# alarm1.net
KiCad netlist of a schematic drawn in EAGLE
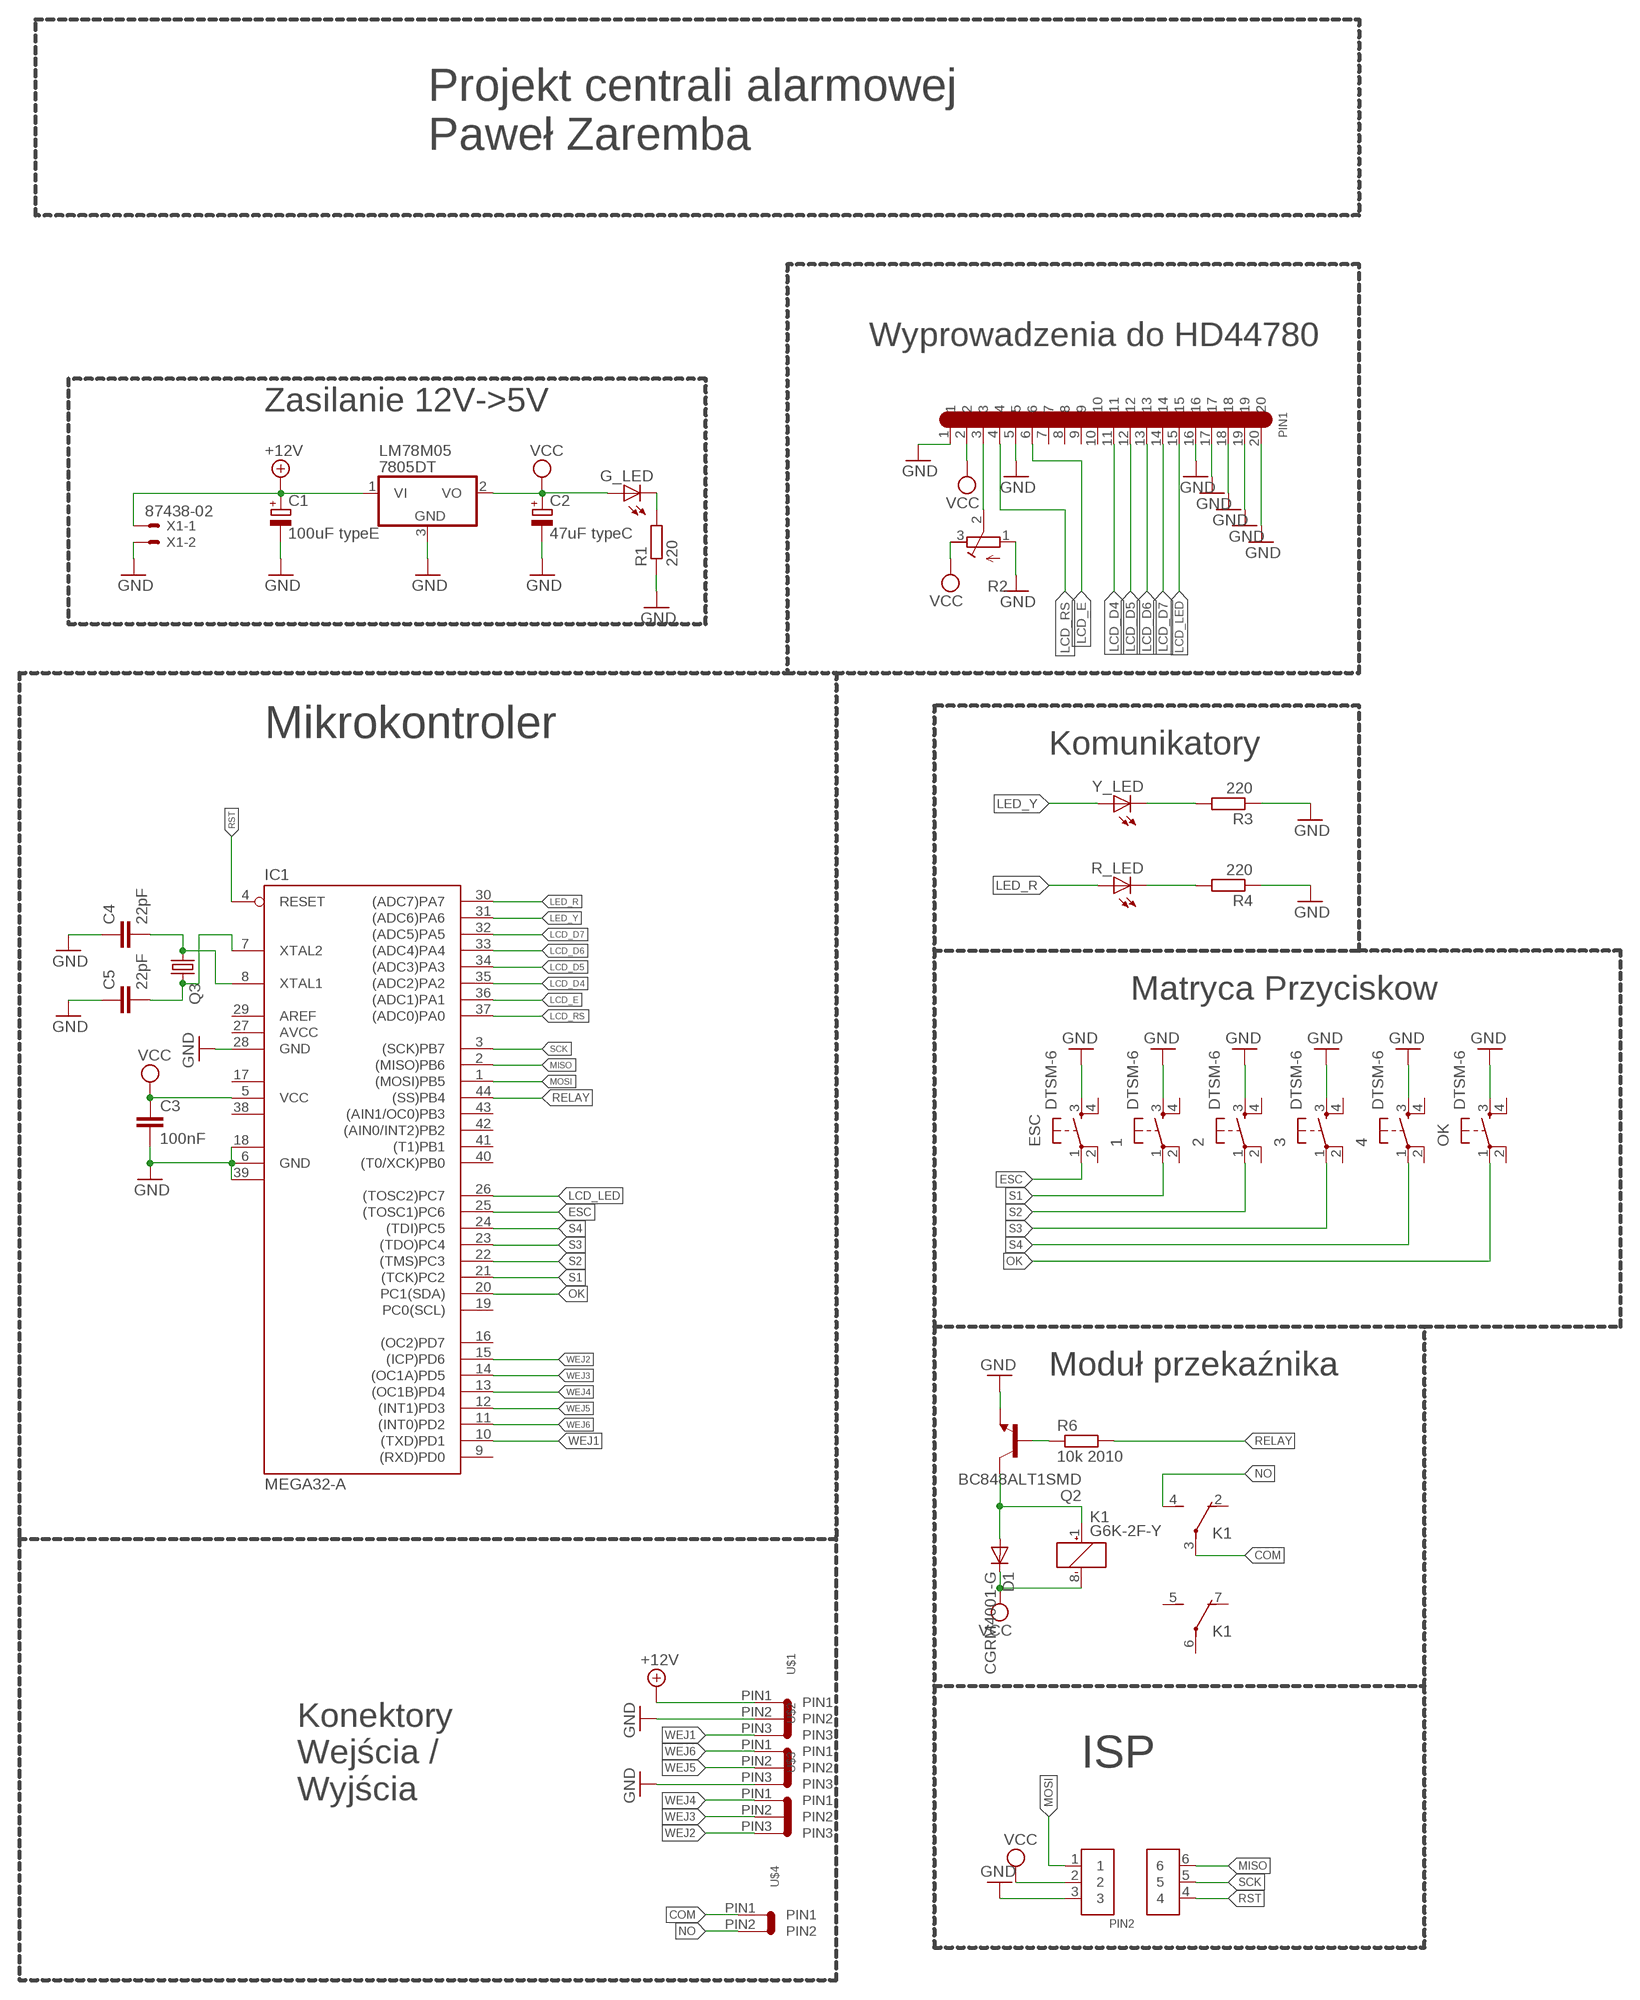
[diagram p0: schematic, sheet 1]

(export (version "E")
  (design (tool "Eeschema 10.0.6"))
  (components
    (comp (ref "1")
      (value "DTSM-6")
      (footprint "eagle-import:DTSM-6")
      (libsource (lib "eagle-import") (part "DTSM-6"))
    )
    (comp (ref "2")
      (value "DTSM-6")
      (footprint "eagle-import:DTSM-6")
      (libsource (lib "eagle-import") (part "DTSM-6"))
    )
    (comp (ref "3")
      (value "DTSM-6")
      (footprint "eagle-import:DTSM-6")
      (libsource (lib "eagle-import") (part "DTSM-6"))
    )
    (comp (ref "4")
      (value "DTSM-6")
      (footprint "eagle-import:DTSM-6")
      (libsource (lib "eagle-import") (part "DTSM-6"))
    )
    (comp (ref "C1")
      (value "100uF typeE")
      (footprint "eagle-import:PANASONIC_E")
      (libsource (lib "eagle-import") (part "CPOL-EUE"))
    )
    (comp (ref "C2")
      (value "47uF typeC")
      (footprint "eagle-import:PANASONIC_C")
      (libsource (lib "eagle-import") (part "CPOL-EUC"))
    )
    (comp (ref "C3")
      (value "100nF")
      (footprint "eagle-import:C1206")
      (libsource (lib "eagle-import") (part "C-EUC1206"))
    )
    (comp (ref "C4")
      (value "22pF")
      (footprint "eagle-import:C1206")
      (libsource (lib "eagle-import") (part "C-EUC1206"))
    )
    (comp (ref "C5")
      (value "22pF")
      (footprint "eagle-import:C1206")
      (libsource (lib "eagle-import") (part "C-EUC1206"))
    )
    (comp (ref "D1")
      (value "CGRM4001-G")
      (footprint "eagle-import:SOD-123_MINI-SMA")
      (libsource (lib "eagle-import") (part "CGRM400-G1"))
    )
    (comp (ref "ESC")
      (value "DTSM-6")
      (footprint "eagle-import:DTSM-6")
      (libsource (lib "eagle-import") (part "DTSM-6"))
    )
    (comp (ref "G_LED")
      (value "LEDCHIPLED_1206")
      (footprint "eagle-import:CHIPLED_1206")
      (libsource (lib "eagle-import") (part "LEDCHIPLED_1206"))
    )
    (comp (ref "IC1")
      (value "MEGA32-A")
      (footprint "eagle-import:TQFP44")
      (libsource (lib "eagle-import") (part "MEGA32-A"))
    )
    (comp (ref "K1")
      (value "G6K-2F-Y")
      (footprint "eagle-import:G6K-2F-Y")
      (fields (field (name "MF") "OMRON COMPONENTS USA") (field (name "MPN") "G6K-2F-Y DC3"))
      (libsource (lib "eagle-import") (part "G6K-2F-Y"))
    )
    (comp (ref "LM78M05")
      (value "7805DT")
      (footprint "eagle-import:TO252")
      (libsource (lib "eagle-import") (part "78DT05"))
    )
    (comp (ref "OK")
      (value "DTSM-6")
      (footprint "eagle-import:DTSM-6")
      (libsource (lib "eagle-import") (part "DTSM-6"))
    )
    (comp (ref "PIN1")
      (value "SINGLE1X20")
      (footprint "eagle-import:SINGLE1X20")
      (libsource (lib "eagle-import") (part "SINGLE1X20"))
    )
    (comp (ref "PIN2")
      (value "2X3_GOLDPIN")
      (footprint "eagle-import:GOLD2X3")
      (libsource (lib "eagle-import") (part "2X3_GOLDPIN"))
    )
    (comp (ref "Q2")
      (value "BC848ALT1SMD")
      (footprint "eagle-import:SOT23")
      (libsource (lib "eagle-import") (part "BC848SMDALT1"))
    )
    (comp (ref "Q3")
      (value "CRYSTALHC49UP")
      (footprint "eagle-import:HC49UP")
      (fields (field (name "OC_FARNELL") "unknown") (field (name "OC_NEWARK") "unknown"))
      (libsource (lib "eagle-import") (part "CRYSTALHC49UP"))
    )
    (comp (ref "R1")
      (value "220")
      (footprint "eagle-import:R1206")
      (libsource (lib "eagle-import") (part "R-EU_R1206"))
    )
    (comp (ref "R2")
      (value "R-TRIMM3314J")
      (footprint "eagle-import:RTRIM3314J")
      (libsource (lib "eagle-import") (part "R-TRIMM3314J"))
    )
    (comp (ref "R3")
      (value "220")
      (footprint "eagle-import:R1206")
      (libsource (lib "eagle-import") (part "R-EU_R1206"))
    )
    (comp (ref "R4")
      (value "220")
      (footprint "eagle-import:R1206")
      (libsource (lib "eagle-import") (part "R-EU_R1206"))
    )
    (comp (ref "R6")
      (value "10k 2010")
      (footprint "eagle-import:R2010")
      (libsource (lib "eagle-import") (part "R-EU_R2010"))
    )
    (comp (ref "R_LED")
      (value "LEDCHIPLED_1206")
      (footprint "eagle-import:CHIPLED_1206")
      (libsource (lib "eagle-import") (part "LEDCHIPLED_1206"))
    )
    (comp (ref "U$1")
      (value "GOLDPIN_SMD_1X3")
      (footprint "eagle-import:GOLDPINSMD1X3")
      (libsource (lib "eagle-import") (part "GOLDPIN_SMD_1X3"))
    )
    (comp (ref "U$2")
      (value "GOLDPIN_SMD_1X3")
      (footprint "eagle-import:GOLDPINSMD1X3")
      (libsource (lib "eagle-import") (part "GOLDPIN_SMD_1X3"))
    )
    (comp (ref "U$3")
      (value "GOLDPIN_SMD_1X3")
      (footprint "eagle-import:GOLDPINSMD1X3")
      (libsource (lib "eagle-import") (part "GOLDPIN_SMD_1X3"))
    )
    (comp (ref "U$4")
      (value "GOLDPIN_SMD_1X2")
      (footprint "eagle-import:GOLDPINSMD1X2")
      (libsource (lib "eagle-import") (part "GOLDPIN_SMD_1X2"))
    )
    (comp (ref "X1")
      (value "87438-02")
      (footprint "eagle-import:87438-02")
      (libsource (lib "eagle-import") (part "87438-02"))
    )
    (comp (ref "Y_LED")
      (value "LEDCHIPLED_1206")
      (footprint "eagle-import:CHIPLED_1206")
      (libsource (lib "eagle-import") (part "LEDCHIPLED_1206"))
    )
  )
  (nets
    (net (code "1") (name "+12V") (class "Default")
      (node (ref "C1") (pin "+") (pinfunction "+_+") (pintype "passive"))
      (node (ref "LM78M05") (pin "1") (pinfunction "VI_1") (pintype "input"))
      (node (ref "U$1") (pin "PIN1") (pinfunction "PIN1_PIN1") (pintype "bidirectional"))
      (node (ref "X1") (pin "1") (pinfunction "S_1") (pintype "passive"))
    )
    (net (code "2") (name "/AVCC") (class "Default")
      (node (ref "IC1") (pin "27") (pinfunction "AVCC_27") (pintype "power_in"))
    )
    (net (code "3") (name "/VCC1") (class "Default")
      (node (ref "IC1") (pin "17") (pinfunction "VCC1_17") (pintype "power_in"))
    )
    (net (code "4") (name "/VCC2") (class "Default")
      (node (ref "IC1") (pin "38") (pinfunction "VCC2_38") (pintype "power_in"))
    )
    (net (code "5") (name "COM") (class "Default")
      (node (ref "K1") (pin "3") (pinfunction "P_3") (pintype "passive"))
      (node (ref "U$4") (pin "PIN1") (pinfunction "PIN1_PIN1") (pintype "bidirectional"))
    )
    (net (code "6") (name "ESC") (class "Default")
      (node (ref "ESC") (pin "1") (pinfunction "1_1") (pintype "passive"))
      (node (ref "IC1") (pin "25") (pinfunction "(TOSC1)PC6_25") (pintype "bidirectional"))
    )
    (net (code "7") (name "GND") (class "Default")
      (node (ref "1") (pin "3") (pinfunction "3_3") (pintype "passive"))
      (node (ref "2") (pin "3") (pinfunction "3_3") (pintype "passive"))
      (node (ref "3") (pin "3") (pinfunction "3_3") (pintype "passive"))
      (node (ref "4") (pin "3") (pinfunction "3_3") (pintype "passive"))
      (node (ref "C1") (pin "-") (pinfunction "-_-") (pintype "passive"))
      (node (ref "C2") (pin "-") (pinfunction "-_-") (pintype "passive"))
      (node (ref "C3") (pin "2") (pinfunction "2_2") (pintype "passive"))
      (node (ref "C4") (pin "1") (pinfunction "1_1") (pintype "passive"))
      (node (ref "C5") (pin "1") (pinfunction "1_1") (pintype "passive"))
      (node (ref "ESC") (pin "3") (pinfunction "3_3") (pintype "passive"))
      (node (ref "IC1") (pin "18") (pinfunction "GND1_18") (pintype "power_in"))
      (node (ref "IC1") (pin "28") (pinfunction "GND_28") (pintype "power_in"))
      (node (ref "IC1") (pin "39") (pinfunction "GND2_39") (pintype "power_in"))
      (node (ref "IC1") (pin "6") (pinfunction "GND_6") (pintype "power_in"))
      (node (ref "LM78M05") (pin "3") (pinfunction "GND_3") (pintype "passive"))
      (node (ref "OK") (pin "3") (pinfunction "3_3") (pintype "passive"))
      (node (ref "PIN1") (pin "1") (pinfunction "1_1") (pintype "passive"))
      (node (ref "PIN1") (pin "16") (pinfunction "16_16") (pintype "passive"))
      (node (ref "PIN1") (pin "17") (pinfunction "17_17") (pintype "passive"))
      (node (ref "PIN1") (pin "18") (pinfunction "18_18") (pintype "passive"))
      (node (ref "PIN1") (pin "19") (pinfunction "19_19") (pintype "passive"))
      (node (ref "PIN1") (pin "20") (pinfunction "20_20") (pintype "passive"))
      (node (ref "PIN1") (pin "5") (pinfunction "5_5") (pintype "passive"))
      (node (ref "PIN2") (pin "3") (pinfunction "3_3") (pintype "passive"))
      (node (ref "Q2") (pin "2") (pinfunction "E_2") (pintype "passive"))
      (node (ref "R1") (pin "1") (pinfunction "1_1") (pintype "passive"))
      (node (ref "R2") (pin "1") (pinfunction "E_1") (pintype "passive"))
      (node (ref "R3") (pin "1") (pinfunction "1_1") (pintype "passive"))
      (node (ref "R4") (pin "1") (pinfunction "1_1") (pintype "passive"))
      (node (ref "U$1") (pin "PIN2") (pinfunction "PIN2_PIN2") (pintype "bidirectional"))
      (node (ref "U$2") (pin "PIN3") (pinfunction "PIN3_PIN3") (pintype "bidirectional"))
      (node (ref "X1") (pin "2") (pinfunction "S_2") (pintype "passive"))
    )
    (net (code "8") (name "LCD_D4") (class "Default")
      (node (ref "IC1") (pin "35") (pinfunction "(ADC2)PA2_35") (pintype "bidirectional"))
      (node (ref "PIN1") (pin "11") (pinfunction "11_11") (pintype "passive"))
    )
    (net (code "9") (name "LCD_D5") (class "Default")
      (node (ref "IC1") (pin "34") (pinfunction "(ADC3)PA3_34") (pintype "bidirectional"))
      (node (ref "PIN1") (pin "12") (pinfunction "12_12") (pintype "passive"))
    )
    (net (code "10") (name "LCD_D6") (class "Default")
      (node (ref "IC1") (pin "33") (pinfunction "(ADC4)PA4_33") (pintype "bidirectional"))
      (node (ref "PIN1") (pin "13") (pinfunction "13_13") (pintype "passive"))
    )
    (net (code "11") (name "LCD_D7") (class "Default")
      (node (ref "IC1") (pin "32") (pinfunction "(ADC5)PA5_32") (pintype "bidirectional"))
      (node (ref "PIN1") (pin "14") (pinfunction "14_14") (pintype "passive"))
    )
    (net (code "12") (name "LCD_E") (class "Default")
      (node (ref "IC1") (pin "36") (pinfunction "(ADC1)PA1_36") (pintype "bidirectional"))
      (node (ref "PIN1") (pin "6") (pinfunction "6_6") (pintype "passive"))
    )
    (net (code "13") (name "LCD_LED") (class "Default")
      (node (ref "IC1") (pin "26") (pinfunction "(TOSC2)PC7_26") (pintype "bidirectional"))
      (node (ref "PIN1") (pin "15") (pinfunction "15_15") (pintype "passive"))
    )
    (net (code "14") (name "LCD_RS") (class "Default")
      (node (ref "IC1") (pin "37") (pinfunction "(ADC0)PA0_37") (pintype "bidirectional"))
      (node (ref "PIN1") (pin "4") (pinfunction "4_4") (pintype "passive"))
    )
    (net (code "15") (name "LED_R") (class "Default")
      (node (ref "IC1") (pin "30") (pinfunction "(ADC7)PA7_30") (pintype "bidirectional"))
      (node (ref "R_LED") (pin "A") (pinfunction "A_A") (pintype "passive"))
    )
    (net (code "16") (name "LED_Y") (class "Default")
      (node (ref "IC1") (pin "31") (pinfunction "(ADC6)PA6_31") (pintype "bidirectional"))
      (node (ref "Y_LED") (pin "A") (pinfunction "A_A") (pintype "passive"))
    )
    (net (code "17") (name "MISO") (class "Default")
      (node (ref "IC1") (pin "2") (pinfunction "(MISO)PB6_2") (pintype "bidirectional"))
      (node (ref "PIN2") (pin "6") (pinfunction "6_6") (pintype "passive"))
    )
    (net (code "18") (name "MOSI") (class "Default")
      (node (ref "IC1") (pin "1") (pinfunction "(MOSI)PB5_1") (pintype "bidirectional"))
      (node (ref "PIN2") (pin "1") (pinfunction "1_1") (pintype "passive"))
    )
    (net (code "19") (name "NO") (class "Default")
      (node (ref "K1") (pin "4") (pinfunction "S_4") (pintype "passive"))
      (node (ref "U$4") (pin "PIN2") (pinfunction "PIN2_PIN2") (pintype "bidirectional"))
    )
    (net (code "20") (name "Net-(G_LED-PadC)") (class "Default")
      (node (ref "G_LED") (pin "C") (pinfunction "C_C") (pintype "passive"))
      (node (ref "R1") (pin "2") (pinfunction "2_2") (pintype "passive"))
    )
    (net (code "21") (name "Net-(IC1-XTAL1)") (class "Default")
      (node (ref "C4") (pin "2") (pinfunction "2_2") (pintype "passive"))
      (node (ref "IC1") (pin "8") (pinfunction "XTAL1_8") (pintype "bidirectional"))
      (node (ref "Q3") (pin "1") (pinfunction "1_1") (pintype "passive"))
    )
    (net (code "22") (name "Net-(IC1-XTAL2)") (class "Default")
      (node (ref "C5") (pin "2") (pinfunction "2_2") (pintype "passive"))
      (node (ref "IC1") (pin "7") (pinfunction "XTAL2_7") (pintype "bidirectional"))
      (node (ref "Q3") (pin "2") (pinfunction "2_2") (pintype "passive"))
    )
    (net (code "23") (name "Net-(K1A-+)") (class "Default")
      (node (ref "D1") (pin "A") (pinfunction "A_A") (pintype "passive"))
      (node (ref "K1") (pin "1") (pinfunction "+_1") (pintype "passive"))
      (node (ref "Q2") (pin "3") (pinfunction "C_3") (pintype "passive"))
    )
    (net (code "24") (name "Net-(Q2-B)") (class "Default")
      (node (ref "Q2") (pin "1") (pinfunction "B_1") (pintype "passive"))
      (node (ref "R6") (pin "1") (pinfunction "1_1") (pintype "passive"))
    )
    (net (code "25") (name "Net-(R2-S)") (class "Default")
      (node (ref "PIN1") (pin "3") (pinfunction "3_3") (pintype "passive"))
      (node (ref "R2") (pin "2") (pinfunction "S_2") (pintype "passive"))
    )
    (net (code "26") (name "Net-(R3-Pad2)") (class "Default")
      (node (ref "R3") (pin "2") (pinfunction "2_2") (pintype "passive"))
      (node (ref "Y_LED") (pin "C") (pinfunction "C_C") (pintype "passive"))
    )
    (net (code "27") (name "Net-(R4-Pad2)") (class "Default")
      (node (ref "R4") (pin "2") (pinfunction "2_2") (pintype "passive"))
      (node (ref "R_LED") (pin "C") (pinfunction "C_C") (pintype "passive"))
    )
    (net (code "28") (name "OK") (class "Default")
      (node (ref "IC1") (pin "20") (pinfunction "PC1(SDA)_20") (pintype "bidirectional"))
      (node (ref "OK") (pin "1") (pinfunction "1_1") (pintype "passive"))
    )
    (net (code "29") (name "RELAY") (class "Default")
      (node (ref "IC1") (pin "44") (pinfunction "(SS)PB4_44") (pintype "bidirectional"))
      (node (ref "R6") (pin "2") (pinfunction "2_2") (pintype "passive"))
    )
    (net (code "30") (name "RST") (class "Default")
      (node (ref "IC1") (pin "4") (pinfunction "RESET_4") (pintype "input"))
      (node (ref "PIN2") (pin "4") (pinfunction "4_4") (pintype "passive"))
    )
    (net (code "31") (name "S1") (class "Default")
      (node (ref "1") (pin "1") (pinfunction "1_1") (pintype "passive"))
      (node (ref "IC1") (pin "21") (pinfunction "(TCK)PC2_21") (pintype "bidirectional"))
    )
    (net (code "32") (name "S2") (class "Default")
      (node (ref "2") (pin "1") (pinfunction "1_1") (pintype "passive"))
      (node (ref "IC1") (pin "22") (pinfunction "(TMS)PC3_22") (pintype "bidirectional"))
    )
    (net (code "33") (name "S3") (class "Default")
      (node (ref "3") (pin "1") (pinfunction "1_1") (pintype "passive"))
      (node (ref "IC1") (pin "23") (pinfunction "(TDO)PC4_23") (pintype "bidirectional"))
    )
    (net (code "34") (name "S4") (class "Default")
      (node (ref "4") (pin "1") (pinfunction "1_1") (pintype "passive"))
      (node (ref "IC1") (pin "24") (pinfunction "(TDI)PC5_24") (pintype "bidirectional"))
    )
    (net (code "35") (name "SCK") (class "Default")
      (node (ref "IC1") (pin "3") (pinfunction "(SCK)PB7_3") (pintype "bidirectional"))
      (node (ref "PIN2") (pin "5") (pinfunction "5_5") (pintype "passive"))
    )
    (net (code "36") (name "VCC") (class "Default")
      (node (ref "C2") (pin "+") (pinfunction "+_+") (pintype "passive"))
      (node (ref "C3") (pin "1") (pinfunction "1_1") (pintype "passive"))
      (node (ref "D1") (pin "C") (pinfunction "C_C") (pintype "passive"))
      (node (ref "G_LED") (pin "A") (pinfunction "A_A") (pintype "passive"))
      (node (ref "IC1") (pin "5") (pinfunction "VCC_5") (pintype "power_in"))
      (node (ref "K1") (pin "8") (pinfunction "-_8") (pintype "passive"))
      (node (ref "LM78M05") (pin "2") (pinfunction "VO_2") (pintype "passive"))
      (node (ref "PIN1") (pin "2") (pinfunction "2_2") (pintype "passive"))
      (node (ref "PIN2") (pin "2") (pinfunction "2_2") (pintype "passive"))
      (node (ref "R2") (pin "3") (pinfunction "A_3") (pintype "passive"))
    )
    (net (code "37") (name "WEJ1") (class "Default")
      (node (ref "IC1") (pin "10") (pinfunction "(TXD)PD1_10") (pintype "bidirectional"))
      (node (ref "U$1") (pin "PIN3") (pinfunction "PIN3_PIN3") (pintype "bidirectional"))
    )
    (net (code "38") (name "WEJ2") (class "Default")
      (node (ref "IC1") (pin "15") (pinfunction "(ICP)PD6_15") (pintype "bidirectional"))
      (node (ref "U$3") (pin "PIN3") (pinfunction "PIN3_PIN3") (pintype "bidirectional"))
    )
    (net (code "39") (name "WEJ3") (class "Default")
      (node (ref "IC1") (pin "14") (pinfunction "(OC1A)PD5_14") (pintype "bidirectional"))
      (node (ref "U$3") (pin "PIN2") (pinfunction "PIN2_PIN2") (pintype "bidirectional"))
    )
    (net (code "40") (name "WEJ4") (class "Default")
      (node (ref "IC1") (pin "13") (pinfunction "(OC1B)PD4_13") (pintype "bidirectional"))
      (node (ref "U$3") (pin "PIN1") (pinfunction "PIN1_PIN1") (pintype "bidirectional"))
    )
    (net (code "41") (name "WEJ5") (class "Default")
      (node (ref "IC1") (pin "12") (pinfunction "(INT1)PD3_12") (pintype "bidirectional"))
      (node (ref "U$2") (pin "PIN2") (pinfunction "PIN2_PIN2") (pintype "bidirectional"))
    )
    (net (code "42") (name "WEJ6") (class "Default")
      (node (ref "IC1") (pin "11") (pinfunction "(INT0)PD2_11") (pintype "bidirectional"))
      (node (ref "U$2") (pin "PIN1") (pinfunction "PIN1_PIN1") (pintype "bidirectional"))
    )
    (net (code "43") (name "unconnected-(1-Pad2)") (class "Default")
      (node (ref "1") (pin "2") (pinfunction "2_2") (pintype "passive"))
    )
    (net (code "44") (name "unconnected-(1-Pad4)") (class "Default")
      (node (ref "1") (pin "4") (pinfunction "4_4") (pintype "passive"))
    )
    (net (code "45") (name "unconnected-(2-Pad2)") (class "Default")
      (node (ref "2") (pin "2") (pinfunction "2_2") (pintype "passive"))
    )
    (net (code "46") (name "unconnected-(2-Pad4)") (class "Default")
      (node (ref "2") (pin "4") (pinfunction "4_4") (pintype "passive"))
    )
    (net (code "47") (name "unconnected-(3-Pad2)") (class "Default")
      (node (ref "3") (pin "2") (pinfunction "2_2") (pintype "passive"))
    )
    (net (code "48") (name "unconnected-(3-Pad4)") (class "Default")
      (node (ref "3") (pin "4") (pinfunction "4_4") (pintype "passive"))
    )
    (net (code "49") (name "unconnected-(4-Pad2)") (class "Default")
      (node (ref "4") (pin "2") (pinfunction "2_2") (pintype "passive"))
    )
    (net (code "50") (name "unconnected-(4-Pad4)") (class "Default")
      (node (ref "4") (pin "4") (pinfunction "4_4") (pintype "passive"))
    )
    (net (code "51") (name "unconnected-(ESC-Pad2)") (class "Default")
      (node (ref "ESC") (pin "2") (pinfunction "2_2") (pintype "passive"))
    )
    (net (code "52") (name "unconnected-(ESC-Pad4)") (class "Default")
      (node (ref "ESC") (pin "4") (pinfunction "4_4") (pintype "passive"))
    )
    (net (code "53") (name "unconnected-(IC1-(AIN0{slash}INT2)PB2-Pad42)") (class "Default")
      (node (ref "IC1") (pin "42") (pinfunction "(AIN0/INT2)PB2_42") (pintype "bidirectional"))
    )
    (net (code "54") (name "unconnected-(IC1-(AIN1{slash}OC0)PB3-Pad43)") (class "Default")
      (node (ref "IC1") (pin "43") (pinfunction "(AIN1/OC0)PB3_43") (pintype "bidirectional"))
    )
    (net (code "55") (name "unconnected-(IC1-(OC2)PD7-Pad16)") (class "Default")
      (node (ref "IC1") (pin "16") (pinfunction "(OC2)PD7_16") (pintype "bidirectional"))
    )
    (net (code "56") (name "unconnected-(IC1-(RXD)PD0-Pad9)") (class "Default")
      (node (ref "IC1") (pin "9") (pinfunction "(RXD)PD0_9") (pintype "bidirectional"))
    )
    (net (code "57") (name "unconnected-(IC1-(T0{slash}XCK)PB0-Pad40)") (class "Default")
      (node (ref "IC1") (pin "40") (pinfunction "(T0/XCK)PB0_40") (pintype "bidirectional"))
    )
    (net (code "58") (name "unconnected-(IC1-(T1)PB1-Pad41)") (class "Default")
      (node (ref "IC1") (pin "41") (pinfunction "(T1)PB1_41") (pintype "bidirectional"))
    )
    (net (code "59") (name "unconnected-(IC1-AREF-Pad29)") (class "Default")
      (node (ref "IC1") (pin "29") (pinfunction "AREF_29") (pintype "passive"))
    )
    (net (code "60") (name "unconnected-(IC1-PC0(SCL)-Pad19)") (class "Default")
      (node (ref "IC1") (pin "19") (pinfunction "PC0(SCL)_19") (pintype "bidirectional"))
    )
    (net (code "61") (name "unconnected-(K1B-O-Pad2)") (class "Default")
      (node (ref "K1") (pin "2") (pinfunction "O_2") (pintype "passive"))
    )
    (net (code "62") (name "unconnected-(K1C-O-Pad7)") (class "Default")
      (node (ref "K1") (pin "7") (pinfunction "O_7") (pintype "passive"))
    )
    (net (code "63") (name "unconnected-(K1C-P-Pad6)") (class "Default")
      (node (ref "K1") (pin "6") (pinfunction "P_6") (pintype "passive"))
    )
    (net (code "64") (name "unconnected-(K1C-S-Pad5)") (class "Default")
      (node (ref "K1") (pin "5") (pinfunction "S_5") (pintype "passive"))
    )
    (net (code "65") (name "unconnected-(OK-Pad2)") (class "Default")
      (node (ref "OK") (pin "2") (pinfunction "2_2") (pintype "passive"))
    )
    (net (code "66") (name "unconnected-(OK-Pad4)") (class "Default")
      (node (ref "OK") (pin "4") (pinfunction "4_4") (pintype "passive"))
    )
    (net (code "67") (name "unconnected-(PIN1-Pad7)") (class "Default")
      (node (ref "PIN1") (pin "7") (pinfunction "7_7") (pintype "passive"))
    )
    (net (code "68") (name "unconnected-(PIN1-Pad8)") (class "Default")
      (node (ref "PIN1") (pin "8") (pinfunction "8_8") (pintype "passive"))
    )
    (net (code "69") (name "unconnected-(PIN1-Pad9)") (class "Default")
      (node (ref "PIN1") (pin "9") (pinfunction "9_9") (pintype "passive"))
    )
    (net (code "70") (name "unconnected-(PIN1-Pad10)") (class "Default")
      (node (ref "PIN1") (pin "10") (pinfunction "10_10") (pintype "passive"))
    )
  )
)
